# MCU_Transceiver_Board.net
KiCad netlist of a schematic drawn in Altium Designer
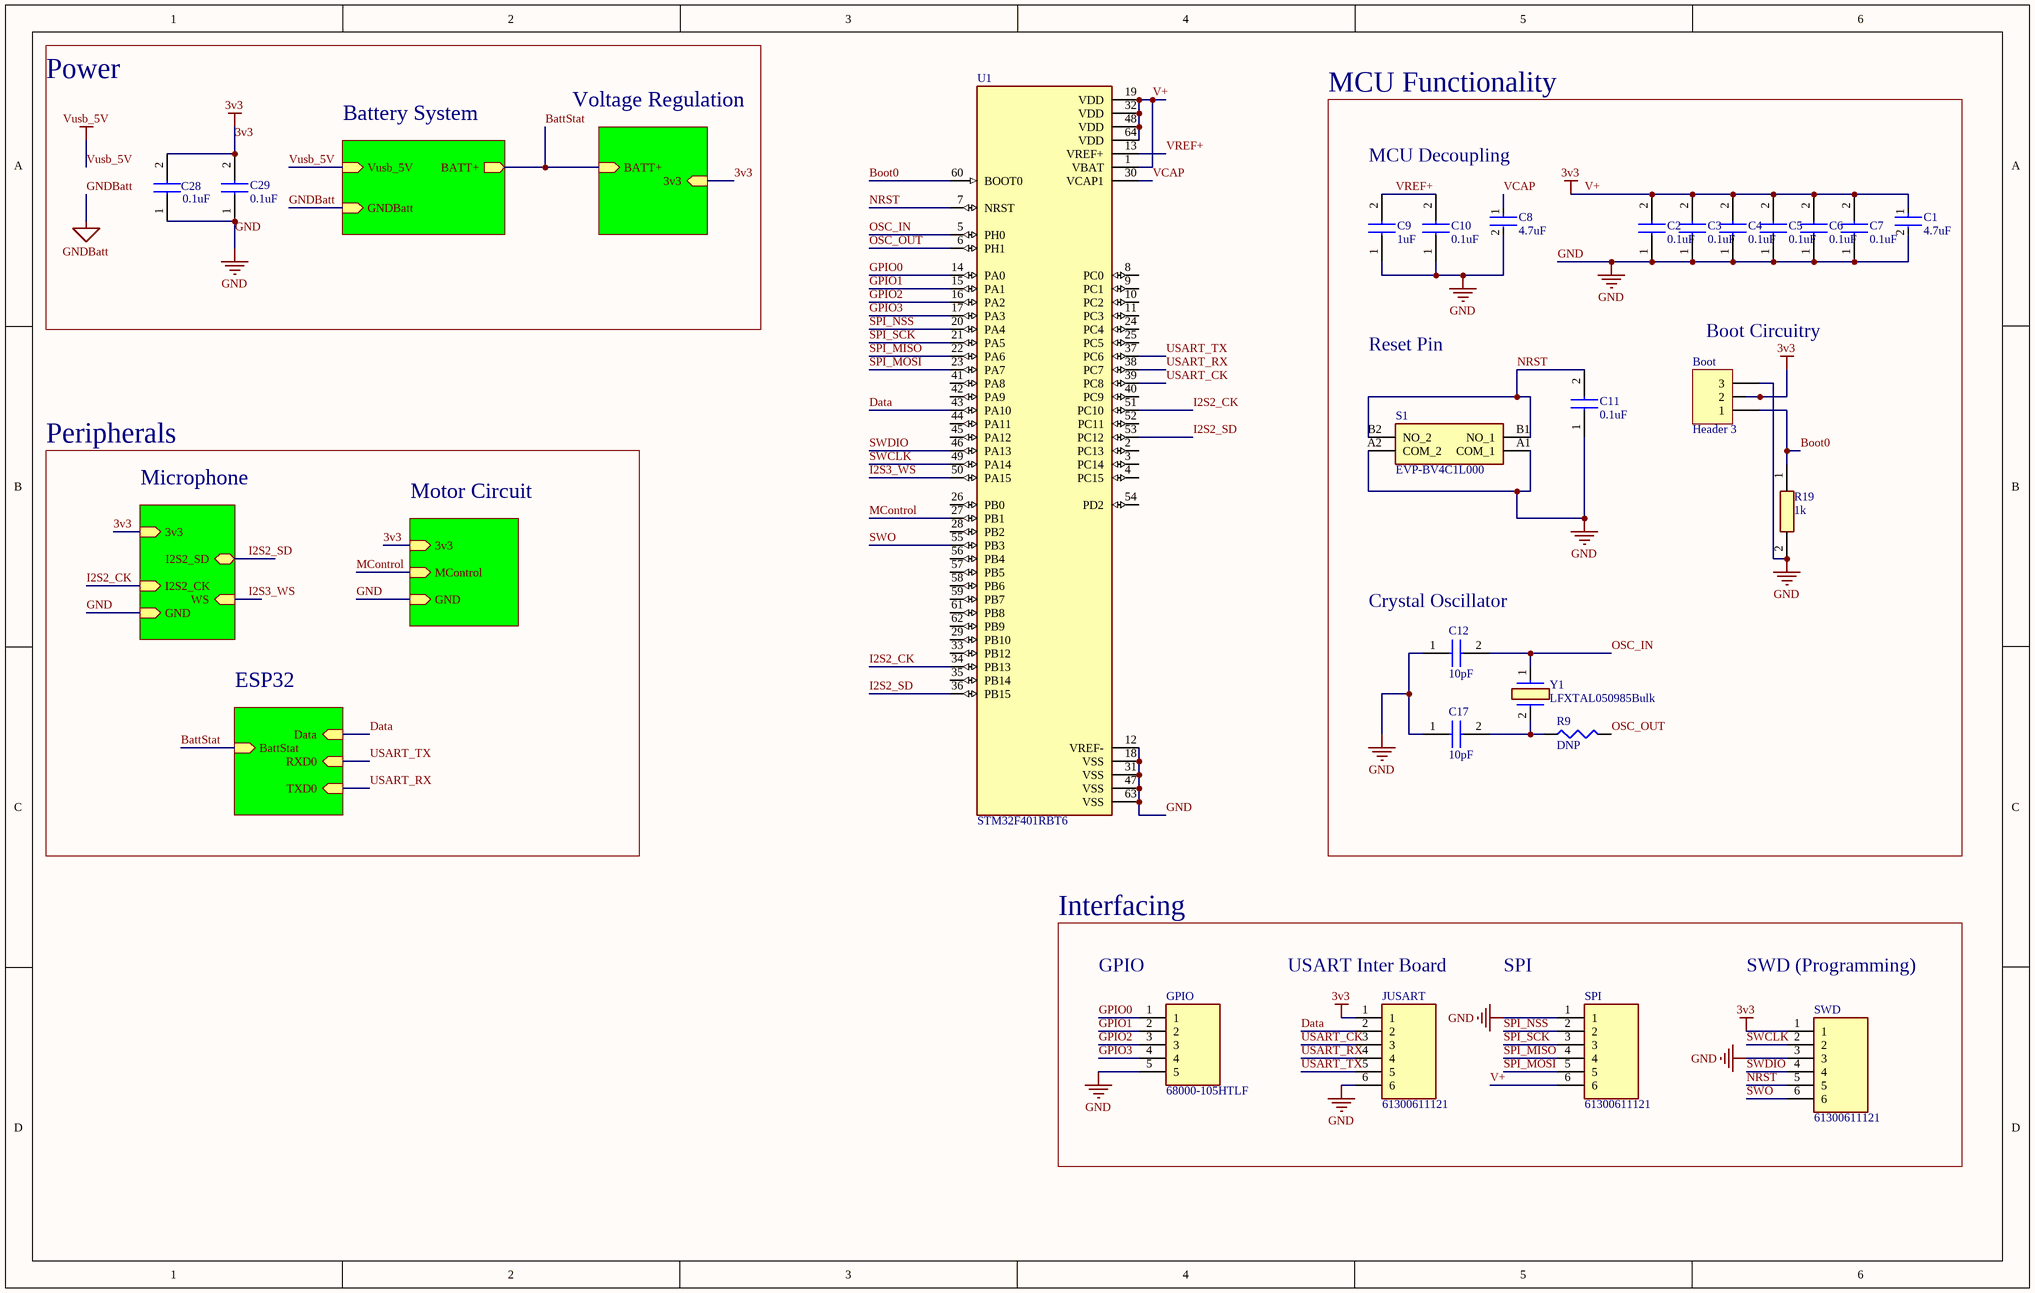
[diagram p0: MCU_Transceiver_Board.SchDoc]

(export (version "E")
  (design (tool "Eeschema 10.0.6"))
  (components
    (comp (ref "Boot")
      (value "Header 3")
      (footprint "HDR1X3")
      (description "Header, 3-Pin")
      (fields (field (name "PUBLISHER") "Altium Limited"))
      (libsource (lib "Miscellaneous Connectors") (part "Header 3"))
    )
    (comp (ref "C1")
      (value "4.7uF")
      (footprint "FP-1206-L_3_2_0_2-W_1_6_0-IPC_B")
      (description "General Purpose Ceramic Capacitor, 1206, 4.7uF, 20%, X5R, 15%, 16V, 1206YD475MAT2A")
      (fields (field (name "TOLERANCE") "20%"))
      (libsource (lib "Altium Content Vault") (part "02cd4be3c70576c341d710602a673aa"))
    )
    (comp (ref "C2")
      (value "0.1uF")
      (footprint "SamacSys:CAPC3216X180N")
      (description "Capacitor, GCM31C5C1H104FA16L, 1206")
      (fields
        (field (name "MANUFACTURER_PART_NUMBER") "GCM31C5C1H104FA16L")
        (field (name "MOUSER PART NUMBER") "81-GCM31C5C1H104FA16")
      )
      (libsource (lib "*") (part "GCM31C5C1H104FA16L"))
    )
    (comp (ref "C3")
      (value "0.1uF")
      (footprint "SamacSys:CAPC3216X180N")
      (description "Capacitor, C5C1H104FA16L")
      (fields
        (field (name "MANUFACTURER_PART_NUMBER") "GCM31C5C1H104FA16L")
        (field (name "MOUSER PART NUMBER") "81-GCM31C5C1H104FA16")
      )
      (libsource (lib "*") (part "GCM31C5C1H104FA16L"))
    )
    (comp (ref "C4")
      (value "0.1uF")
      (footprint "SamacSys:CAPC3216X180N")
      (description "Capacitor, C5C1H104FA16L")
      (fields
        (field (name "MANUFACTURER_PART_NUMBER") "GCM31C5C1H104FA16L")
        (field (name "MOUSER PART NUMBER") "81-GCM31C5C1H104FA16")
      )
      (libsource (lib "*") (part "GCM31C5C1H104FA16L"))
    )
    (comp (ref "C5")
      (value "0.1uF")
      (footprint "SamacSys:CAPC3216X180N")
      (description "Capacitor, C5C1H104FA16L")
      (fields
        (field (name "MANUFACTURER_PART_NUMBER") "GCM31C5C1H104FA16L")
        (field (name "MOUSER PART NUMBER") "81-GCM31C5C1H104FA16")
      )
      (libsource (lib "*") (part "GCM31C5C1H104FA16L"))
    )
    (comp (ref "C6")
      (value "0.1uF")
      (footprint "SamacSys:CAPC3216X180N")
      (description "Capacitor, C5C1H104FA16L")
      (fields
        (field (name "MANUFACTURER_PART_NUMBER") "GCM31C5C1H104FA16L")
        (field (name "MOUSER PART NUMBER") "81-GCM31C5C1H104FA16")
      )
      (libsource (lib "*") (part "GCM31C5C1H104FA16L"))
    )
    (comp (ref "C7")
      (value "0.1uF")
      (footprint "SamacSys:CAPC3216X180N")
      (description "Capacitor, C5C1H104FA16L")
      (fields
        (field (name "MANUFACTURER_PART_NUMBER") "GCM31C5C1H104FA16L")
        (field (name "MOUSER PART NUMBER") "81-GCM31C5C1H104FA16")
      )
      (libsource (lib "*") (part "GCM31C5C1H104FA16L"))
    )
    (comp (ref "C8")
      (value "4.7uF")
      (footprint "FP-1206-L_3_2_0_2-W_1_6_0-IPC_B")
      (description "General Purpose Ceramic Capacitor, 1206, 4.7uF, 20%, X5R, 15%, 16V, 1206YD475MAT2A")
      (fields (field (name "TOLERANCE") "20%"))
      (libsource (lib "Altium Content Vault") (part "02cd4be3c70576c341d710602a673aa"))
    )
    (comp (ref "C9")
      (value "1uF")
      (footprint "SamacSys:CAPC1608X90N")
      (description "Capacitor, 0603YC10JAT2A")
      (fields
        (field (name "MANUFACTURER_PART_NUMBER") "0603YC105JAT2A")
        (field (name "MOUSER PART NUMBER") "581-0603YC105JAT2A")
      )
      (libsource (lib "*") (part "0603YC105JAT2A"))
    )
    (comp (ref "C10")
      (value "0.1uF")
      (footprint "SamacSys:CAPC3216X180N")
      (description "Capacitor, GCM31C5C1H104FA16L, 1206")
      (fields
        (field (name "MANUFACTURER_PART_NUMBER") "GCM31C5C1H104FA16L")
        (field (name "MOUSER PART NUMBER") "81-GCM31C5C1H104FA16")
      )
      (libsource (lib "*") (part "GCM31C5C1H104FA16L"))
    )
    (comp (ref "C11")
      (value "0.1uF")
      (footprint "SamacSys:CAPC3216X180N")
      (description "Capacitor, GCM31C5C1H104FA16L, 1206")
      (fields
        (field (name "MANUFACTURER_PART_NUMBER") "GCM31C5C1H104FA16L")
        (field (name "MOUSER PART NUMBER") "81-GCM31C5C1H104FA16")
      )
      (libsource (lib "*") (part "GCM31C5C1H104FA16L"))
    )
    (comp (ref "C12")
      (value "10pF")
      (footprint "SamacSys:CAPC1608X90N")
      (description "Capacitor, 10pF, 06035A100F4T4A")
      (fields
        (field (name "MANUFACTURER_PART_NUMBER") "06035A100F4T4A")
        (field (name "MOUSER PART NUMBER") "581-06035A100F4T4A")
      )
      (libsource (lib "*") (part "06035A100F4T4A"))
    )
    (comp (ref "C17")
      (value "10pF")
      (footprint "SamacSys:CAPC1608X90N")
      (description "Capacitor, 10pF, 06035A100F4T4A")
      (fields
        (field (name "MANUFACTURER_PART_NUMBER") "06035A100F4T4A")
        (field (name "MOUSER PART NUMBER") "581-06035A100F4T4A")
      )
      (libsource (lib "*") (part "06035A100F4T4A"))
    )
    (comp (ref "C28")
      (value "0.1uF")
      (footprint "SamacSys:CAPC3216X180N")
      (description "Capacitor, GCM31C5C1H104FA16L, 1206")
      (fields
        (field (name "MANUFACTURER_PART_NUMBER") "GCM31C5C1H104FA16L")
        (field (name "MOUSER PART NUMBER") "81-GCM31C5C1H104FA16")
      )
      (libsource (lib "*") (part "GCM31C5C1H104FA16L"))
    )
    (comp (ref "C29")
      (value "0.1uF")
      (footprint "SamacSys:CAPC3216X180N")
      (description "Capacitor, GCM31C5C1H104FA16L, 1206")
      (fields
        (field (name "MANUFACTURER_PART_NUMBER") "GCM31C5C1H104FA16L")
        (field (name "MOUSER PART NUMBER") "81-GCM31C5C1H104FA16")
      )
      (libsource (lib "*") (part "GCM31C5C1H104FA16L"))
    )
    (comp (ref "GPIO")
      (value "68000-105HTLF")
      (footprint "SamacSys:HDRV5W67P0X254_1X5_1270X241X858P")
      (description "Connector")
      (fields (field (name "MOUSER PART NUMBER") "649-68000-105HTLF"))
      (libsource (lib "*") (part "68000-105HTLF"))
    )
    (comp (ref "JUSART")
      (value "61300611121")
      (footprint "SamacSys:HDRV6W64P0X254_1X6_1524X254X869P")
      (description "Connector")
      (fields (field (name "MOUSER PART NUMBER") "710-61300611121"))
      (libsource (lib "*") (part "61300611121"))
    )
    (comp (ref "R9")
      (value "DNP")
      (footprint "J1-0603")
      (description "Resistor")
      (fields (field (name "Comment") "Res3") (field (name "PUBLISHER") "Altium Limited"))
      (libsource (lib "Miscellaneous Devices") (part "Res3"))
    )
    (comp (ref "R19")
      (value "1k")
      (footprint "SamacSys:RESC3016X65N")
      (description "Resistor, CRT1206-FZ-1001ELF")
      (fields
        (field (name "MANUFACTURER_PART_NUMBER") "CRT1206-FZ-1001ELF")
        (field (name "MOUSER PART NUMBER") "652-CRT1206FZ1001ELF")
      )
      (libsource (lib "*") (part "CRT1206-FZ-1001ELF"))
    )
    (comp (ref "S1")
      (value "EVP-BV4C1L000")
      (footprint "SamacSys:EVPBV4C1L000")
      (description "Switch")
      (fields (field (name "MOUSER PART NUMBER") "667-EVP-BV4C1L000"))
      (libsource (lib "*") (part "EVP-BV4C1L000"))
    )
    (comp (ref "SPI")
      (value "61300611121")
      (footprint "SamacSys:HDRV6W64P0X254_1X6_1524X254X869P")
      (description "Connector")
      (fields (field (name "MOUSER PART NUMBER") "710-61300611121"))
      (libsource (lib "*") (part "61300611121"))
    )
    (comp (ref "SWD")
      (value "61300611121")
      (footprint "SamacSys:HDRV6W64P0X254_1X6_1524X254X869P")
      (description "Connector")
      (fields (field (name "MOUSER PART NUMBER") "710-61300611121"))
      (libsource (lib "*") (part "61300611121"))
    )
    (comp (ref "U1")
      (value "STM32F401RBT6")
      (footprint "QFP50P1200X1200X160-64N")
      (description "ARMÂ® CortexÂ®-M4 STM32F4 Microcontroller IC 32-Bit 84MHz 128KB _128K x 8_ FLASH 64-LQFP _10x10_")
      (fields (field (name "MF") "STMicroelectronics"))
      (libsource (lib "STM32F401RBT6") (part "STM32F401RBT6"))
    )
    (comp (ref "Y1")
      (value "LFXTAL050985Bulk")
      (footprint "SamacSys:LFXTAL050985Bulk")
      (description "Crystal or Oscillator")
      (fields (field (name "MOUSER PART NUMBER") "449-LFXTAL050985BULK"))
      (libsource (lib "*") (part "LFXTAL050985Bulk"))
    )
  )
  (nets
    (net (code "2") (name "/Boot0") (class "Default")
      (node (ref "Boot") (pin "1") (pinfunction "1_1") (pintype "passive"))
      (node (ref "R19") (pin "1") (pinfunction "1_1") (pintype "passive"))
      (node (ref "U1") (pin "60") (pinfunction "BOOT0_60") (pintype "input"))
    )
    (net (code "3") (name "/Data") (class "Default")
      (node (ref "JUSART") (pin "2") (pinfunction "2_2") (pintype "passive"))
      (node (ref "U1") (pin "43") (pinfunction "PA10_43") (pintype "bidirectional"))
    )
    (net (code "4") (name "/GPIO0") (class "Default")
      (node (ref "GPIO") (pin "1") (pinfunction "1_1") (pintype "passive"))
      (node (ref "U1") (pin "14") (pinfunction "PA0_14") (pintype "bidirectional"))
    )
    (net (code "5") (name "/GPIO1") (class "Default")
      (node (ref "GPIO") (pin "2") (pinfunction "2_2") (pintype "passive"))
      (node (ref "U1") (pin "15") (pinfunction "PA1_15") (pintype "bidirectional"))
    )
    (net (code "6") (name "/GPIO2") (class "Default")
      (node (ref "GPIO") (pin "3") (pinfunction "3_3") (pintype "passive"))
      (node (ref "U1") (pin "16") (pinfunction "PA2_16") (pintype "bidirectional"))
    )
    (net (code "7") (name "/GPIO3") (class "Default")
      (node (ref "GPIO") (pin "4") (pinfunction "4_4") (pintype "passive"))
      (node (ref "U1") (pin "17") (pinfunction "PA3_17") (pintype "bidirectional"))
    )
    (net (code "8") (name "/I2S2_CK") (class "Default")
      (node (ref "U1") (pin "34") (pinfunction "PB13_34") (pintype "bidirectional"))
      (node (ref "U1") (pin "51") (pinfunction "PC10_51") (pintype "bidirectional"))
    )
    (net (code "9") (name "/I2S2_SD") (class "Default")
      (node (ref "U1") (pin "36") (pinfunction "PB15_36") (pintype "bidirectional"))
      (node (ref "U1") (pin "53") (pinfunction "PC12_53") (pintype "bidirectional"))
    )
    (net (code "10") (name "/I2S3_WS") (class "Default")
      (node (ref "U1") (pin "50") (pinfunction "PA15_50") (pintype "bidirectional"))
    )
    (net (code "11") (name "/MControl") (class "Default")
      (node (ref "U1") (pin "27") (pinfunction "PB1_27") (pintype "bidirectional"))
    )
    (net (code "12") (name "/NRST") (class "Default")
      (node (ref "C11") (pin "2") (pinfunction "2_2") (pintype "passive"))
      (node (ref "S1") (pin "B1") (pinfunction "NO_1_B1") (pintype "passive"))
      (node (ref "S1") (pin "B2") (pinfunction "NO_2_B2") (pintype "passive"))
      (node (ref "SWD") (pin "5") (pinfunction "5_5") (pintype "passive"))
      (node (ref "U1") (pin "7") (pinfunction "NRST_7") (pintype "bidirectional"))
    )
    (net (code "13") (name "/OSC_IN") (class "Default")
      (node (ref "C12") (pin "2") (pinfunction "2_2") (pintype "passive"))
      (node (ref "U1") (pin "5") (pinfunction "PH0_5") (pintype "bidirectional"))
      (node (ref "Y1") (pin "1") (pinfunction "1_1") (pintype "passive"))
    )
    (net (code "14") (name "/OSC_OUT") (class "Default")
      (node (ref "R9") (pin "2") (pinfunction "2_2") (pintype "passive"))
      (node (ref "U1") (pin "6") (pinfunction "PH1_6") (pintype "bidirectional"))
    )
    (net (code "15") (name "/SPI_MISO") (class "Default")
      (node (ref "SPI") (pin "4") (pinfunction "4_4") (pintype "passive"))
      (node (ref "U1") (pin "22") (pinfunction "PA6_22") (pintype "bidirectional"))
    )
    (net (code "16") (name "/SPI_MOSI") (class "Default")
      (node (ref "SPI") (pin "5") (pinfunction "5_5") (pintype "passive"))
      (node (ref "U1") (pin "23") (pinfunction "PA7_23") (pintype "bidirectional"))
    )
    (net (code "17") (name "/SPI_NSS") (class "Default")
      (node (ref "SPI") (pin "2") (pinfunction "2_2") (pintype "passive"))
      (node (ref "U1") (pin "20") (pinfunction "PA4_20") (pintype "bidirectional"))
    )
    (net (code "18") (name "/SPI_SCK") (class "Default")
      (node (ref "SPI") (pin "3") (pinfunction "3_3") (pintype "passive"))
      (node (ref "U1") (pin "21") (pinfunction "PA5_21") (pintype "bidirectional"))
    )
    (net (code "19") (name "/SWCLK") (class "Default")
      (node (ref "SWD") (pin "2") (pinfunction "2_2") (pintype "passive"))
      (node (ref "U1") (pin "49") (pinfunction "PA14_49") (pintype "bidirectional"))
    )
    (net (code "20") (name "/SWDIO") (class "Default")
      (node (ref "SWD") (pin "4") (pinfunction "4_4") (pintype "passive"))
      (node (ref "U1") (pin "46") (pinfunction "PA13_46") (pintype "bidirectional"))
    )
    (net (code "21") (name "/SWO") (class "Default")
      (node (ref "SWD") (pin "6") (pinfunction "6_6") (pintype "passive"))
      (node (ref "U1") (pin "55") (pinfunction "PB3_55") (pintype "bidirectional"))
    )
    (net (code "22") (name "/USART_CK") (class "Default")
      (node (ref "JUSART") (pin "3") (pinfunction "3_3") (pintype "passive"))
      (node (ref "U1") (pin "39") (pinfunction "PC8_39") (pintype "bidirectional"))
    )
    (net (code "23") (name "/USART_RX") (class "Default")
      (node (ref "JUSART") (pin "4") (pinfunction "4_4") (pintype "passive"))
      (node (ref "U1") (pin "38") (pinfunction "PC7_38") (pintype "bidirectional"))
    )
    (net (code "24") (name "/USART_TX") (class "Default")
      (node (ref "JUSART") (pin "5") (pinfunction "5_5") (pintype "passive"))
      (node (ref "U1") (pin "37") (pinfunction "PC6_37") (pintype "bidirectional"))
    )
    (net (code "25") (name "/VCAP") (class "Default")
      (node (ref "C8") (pin "1") (pinfunction "1_1") (pintype "passive"))
      (node (ref "U1") (pin "30") (pinfunction "VCAP1_30") (pintype "power_in"))
    )
    (net (code "26") (name "/VREF+") (class "Default")
      (node (ref "C10") (pin "2") (pinfunction "2_2") (pintype "passive"))
      (node (ref "C9") (pin "2") (pinfunction "2_2") (pintype "passive"))
      (node (ref "U1") (pin "13") (pinfunction "VREF+_13") (pintype "power_in"))
    )
    (net (code "27") (name "3v3") (class "Default")
      (node (ref "Boot") (pin "2") (pinfunction "2_2") (pintype "passive"))
      (node (ref "C1") (pin "1") (pinfunction "1_1") (pintype "passive"))
      (node (ref "C2") (pin "2") (pinfunction "2_2") (pintype "passive"))
      (node (ref "C28") (pin "2") (pinfunction "2_2") (pintype "passive"))
      (node (ref "C29") (pin "2") (pinfunction "2_2") (pintype "passive"))
      (node (ref "C3") (pin "2") (pinfunction "2_2") (pintype "passive"))
      (node (ref "C4") (pin "2") (pinfunction "2_2") (pintype "passive"))
      (node (ref "C5") (pin "2") (pinfunction "2_2") (pintype "passive"))
      (node (ref "C6") (pin "2") (pinfunction "2_2") (pintype "passive"))
      (node (ref "C7") (pin "2") (pinfunction "2_2") (pintype "passive"))
      (node (ref "JUSART") (pin "1") (pinfunction "1_1") (pintype "passive"))
      (node (ref "SPI") (pin "6") (pinfunction "6_6") (pintype "passive"))
      (node (ref "SWD") (pin "1") (pinfunction "1_1") (pintype "passive"))
      (node (ref "U1") (pin "1") (pinfunction "VBAT_1") (pintype "power_in"))
      (node (ref "U1") (pin "19") (pinfunction "VDD_19") (pintype "power_in"))
      (node (ref "U1") (pin "32") (pinfunction "VDD_32") (pintype "power_in"))
      (node (ref "U1") (pin "48") (pinfunction "VDD_48") (pintype "power_in"))
      (node (ref "U1") (pin "64") (pinfunction "VDD_64") (pintype "power_in"))
    )
    (net (code "28") (name "GND") (class "Default")
      (node (ref "Boot") (pin "3") (pinfunction "3_3") (pintype "passive"))
      (node (ref "C1") (pin "2") (pinfunction "2_2") (pintype "passive"))
      (node (ref "C10") (pin "1") (pinfunction "1_1") (pintype "passive"))
      (node (ref "C11") (pin "1") (pinfunction "1_1") (pintype "passive"))
      (node (ref "C12") (pin "1") (pinfunction "1_1") (pintype "passive"))
      (node (ref "C17") (pin "1") (pinfunction "1_1") (pintype "passive"))
      (node (ref "C2") (pin "1") (pinfunction "1_1") (pintype "passive"))
      (node (ref "C28") (pin "1") (pinfunction "1_1") (pintype "passive"))
      (node (ref "C29") (pin "1") (pinfunction "1_1") (pintype "passive"))
      (node (ref "C3") (pin "1") (pinfunction "1_1") (pintype "passive"))
      (node (ref "C4") (pin "1") (pinfunction "1_1") (pintype "passive"))
      (node (ref "C5") (pin "1") (pinfunction "1_1") (pintype "passive"))
      (node (ref "C6") (pin "1") (pinfunction "1_1") (pintype "passive"))
      (node (ref "C7") (pin "1") (pinfunction "1_1") (pintype "passive"))
      (node (ref "C8") (pin "2") (pinfunction "2_2") (pintype "passive"))
      (node (ref "C9") (pin "1") (pinfunction "1_1") (pintype "passive"))
      (node (ref "GPIO") (pin "5") (pinfunction "5_5") (pintype "passive"))
      (node (ref "JUSART") (pin "6") (pinfunction "6_6") (pintype "passive"))
      (node (ref "R19") (pin "2") (pinfunction "2_2") (pintype "passive"))
      (node (ref "S1") (pin "A1") (pinfunction "COM_1_A1") (pintype "passive"))
      (node (ref "S1") (pin "A2") (pinfunction "COM_2_A2") (pintype "passive"))
      (node (ref "SPI") (pin "1") (pinfunction "1_1") (pintype "passive"))
      (node (ref "SWD") (pin "3") (pinfunction "3_3") (pintype "passive"))
      (node (ref "U1") (pin "12") (pinfunction "VREF-_12") (pintype "power_in"))
      (node (ref "U1") (pin "18") (pinfunction "VSS_18") (pintype "power_in"))
      (node (ref "U1") (pin "31") (pinfunction "VSS_31") (pintype "power_in"))
      (node (ref "U1") (pin "47") (pinfunction "VSS_47") (pintype "power_in"))
      (node (ref "U1") (pin "63") (pinfunction "VSS_63") (pintype "power_in"))
    )
    (net (code "30") (name "Net-(C17-Pad2)") (class "Default")
      (node (ref "C17") (pin "2") (pinfunction "2_2") (pintype "passive"))
      (node (ref "R9") (pin "1") (pinfunction "1_1") (pintype "passive"))
      (node (ref "Y1") (pin "2") (pinfunction "2_2") (pintype "passive"))
    )
    (net (code "32") (name "unconnected-(U1-PA8-Pad41)") (class "Default")
      (node (ref "U1") (pin "41") (pinfunction "PA8_41") (pintype "bidirectional"))
    )
    (net (code "33") (name "unconnected-(U1-PA9-Pad42)") (class "Default")
      (node (ref "U1") (pin "42") (pinfunction "PA9_42") (pintype "bidirectional"))
    )
    (net (code "34") (name "unconnected-(U1-PA11-Pad44)") (class "Default")
      (node (ref "U1") (pin "44") (pinfunction "PA11_44") (pintype "bidirectional"))
    )
    (net (code "35") (name "unconnected-(U1-PA12-Pad45)") (class "Default")
      (node (ref "U1") (pin "45") (pinfunction "PA12_45") (pintype "bidirectional"))
    )
    (net (code "36") (name "unconnected-(U1-PB0-Pad26)") (class "Default")
      (node (ref "U1") (pin "26") (pinfunction "PB0_26") (pintype "bidirectional"))
    )
    (net (code "37") (name "unconnected-(U1-PB2-Pad28)") (class "Default")
      (node (ref "U1") (pin "28") (pinfunction "PB2_28") (pintype "bidirectional"))
    )
    (net (code "38") (name "unconnected-(U1-PB4-Pad56)") (class "Default")
      (node (ref "U1") (pin "56") (pinfunction "PB4_56") (pintype "bidirectional"))
    )
    (net (code "39") (name "unconnected-(U1-PB5-Pad57)") (class "Default")
      (node (ref "U1") (pin "57") (pinfunction "PB5_57") (pintype "bidirectional"))
    )
    (net (code "40") (name "unconnected-(U1-PB6-Pad58)") (class "Default")
      (node (ref "U1") (pin "58") (pinfunction "PB6_58") (pintype "bidirectional"))
    )
    (net (code "41") (name "unconnected-(U1-PB7-Pad59)") (class "Default")
      (node (ref "U1") (pin "59") (pinfunction "PB7_59") (pintype "bidirectional"))
    )
    (net (code "42") (name "unconnected-(U1-PB8-Pad61)") (class "Default")
      (node (ref "U1") (pin "61") (pinfunction "PB8_61") (pintype "bidirectional"))
    )
    (net (code "43") (name "unconnected-(U1-PB9-Pad62)") (class "Default")
      (node (ref "U1") (pin "62") (pinfunction "PB9_62") (pintype "bidirectional"))
    )
    (net (code "44") (name "unconnected-(U1-PB10-Pad29)") (class "Default")
      (node (ref "U1") (pin "29") (pinfunction "PB10_29") (pintype "bidirectional"))
    )
    (net (code "45") (name "unconnected-(U1-PB12-Pad33)") (class "Default")
      (node (ref "U1") (pin "33") (pinfunction "PB12_33") (pintype "bidirectional"))
    )
    (net (code "46") (name "unconnected-(U1-PB14-Pad35)") (class "Default")
      (node (ref "U1") (pin "35") (pinfunction "PB14_35") (pintype "bidirectional"))
    )
    (net (code "47") (name "unconnected-(U1-PC0-Pad8)") (class "Default")
      (node (ref "U1") (pin "8") (pinfunction "PC0_8") (pintype "bidirectional"))
    )
    (net (code "48") (name "unconnected-(U1-PC1-Pad9)") (class "Default")
      (node (ref "U1") (pin "9") (pinfunction "PC1_9") (pintype "bidirectional"))
    )
    (net (code "49") (name "unconnected-(U1-PC2-Pad10)") (class "Default")
      (node (ref "U1") (pin "10") (pinfunction "PC2_10") (pintype "bidirectional"))
    )
    (net (code "50") (name "unconnected-(U1-PC3-Pad11)") (class "Default")
      (node (ref "U1") (pin "11") (pinfunction "PC3_11") (pintype "bidirectional"))
    )
    (net (code "51") (name "unconnected-(U1-PC4-Pad24)") (class "Default")
      (node (ref "U1") (pin "24") (pinfunction "PC4_24") (pintype "bidirectional"))
    )
    (net (code "52") (name "unconnected-(U1-PC5-Pad25)") (class "Default")
      (node (ref "U1") (pin "25") (pinfunction "PC5_25") (pintype "bidirectional"))
    )
    (net (code "53") (name "unconnected-(U1-PC9-Pad40)") (class "Default")
      (node (ref "U1") (pin "40") (pinfunction "PC9_40") (pintype "bidirectional"))
    )
    (net (code "54") (name "unconnected-(U1-PC11-Pad52)") (class "Default")
      (node (ref "U1") (pin "52") (pinfunction "PC11_52") (pintype "bidirectional"))
    )
    (net (code "55") (name "unconnected-(U1-PC13-Pad2)") (class "Default")
      (node (ref "U1") (pin "2") (pinfunction "PC13_2") (pintype "bidirectional"))
    )
    (net (code "56") (name "unconnected-(U1-PC14-Pad3)") (class "Default")
      (node (ref "U1") (pin "3") (pinfunction "PC14_3") (pintype "bidirectional"))
    )
    (net (code "57") (name "unconnected-(U1-PC15-Pad4)") (class "Default")
      (node (ref "U1") (pin "4") (pinfunction "PC15_4") (pintype "bidirectional"))
    )
    (net (code "58") (name "unconnected-(U1-PD2-Pad54)") (class "Default")
      (node (ref "U1") (pin "54") (pinfunction "PD2_54") (pintype "bidirectional"))
    )
  )
)
